# STLink-V2-1.net
KiCad netlist of a schematic drawn in Altium Designer
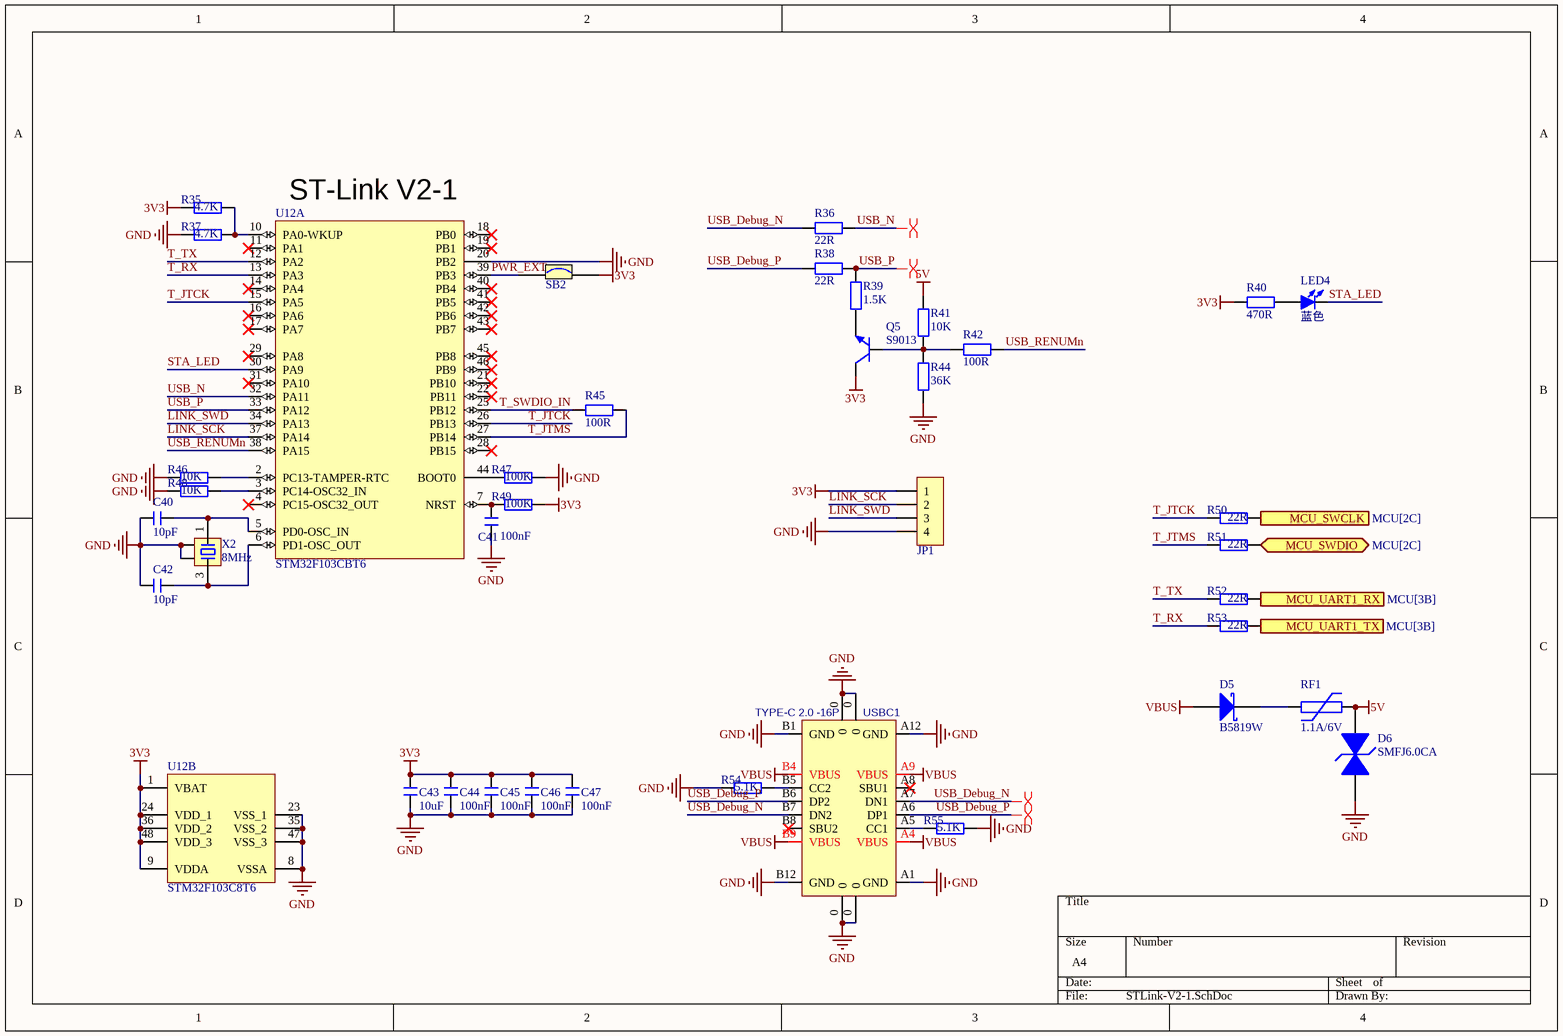
[diagram p0: STLink-V2-1.SchDoc]

(export (version "E")
  (design (tool "Eeschema 10.0.6"))
  (components
    (comp (ref "C40")
      (value "10pF")
      (footprint "C 0402_L")
      (description "无极性贴片电容")
      (fields (field (name "版权归属") "源创客"))
      (libsource (lib "源创客") (part "C"))
    )
    (comp (ref "C41")
      (value "100nF")
      (footprint "C 0402_L")
      (description "无极性贴片电容")
      (fields (field (name "版权归属") "源创客"))
      (libsource (lib "源创客") (part "C"))
    )
    (comp (ref "C42")
      (value "10pF")
      (footprint "C 0402_L")
      (description "无极性贴片电容")
      (fields (field (name "版权归属") "源创客"))
      (libsource (lib "源创客") (part "C"))
    )
    (comp (ref "C43")
      (value "10uF")
      (footprint "C 0402_L")
      (description "无极性贴片电容")
      (fields (field (name "版权归属") "源创客"))
      (libsource (lib "源创客") (part "C"))
    )
    (comp (ref "C44")
      (value "100nF")
      (footprint "C 0402_L")
      (description "无极性贴片电容")
      (fields (field (name "版权归属") "源创客"))
      (libsource (lib "源创客") (part "C"))
    )
    (comp (ref "C45")
      (value "100nF")
      (footprint "C 0402_L")
      (description "无极性贴片电容")
      (fields (field (name "版权归属") "源创客"))
      (libsource (lib "源创客") (part "C"))
    )
    (comp (ref "C46")
      (value "100nF")
      (footprint "C 0402_L")
      (description "无极性贴片电容")
      (fields (field (name "版权归属") "源创客"))
      (libsource (lib "源创客") (part "C"))
    )
    (comp (ref "C47")
      (value "100nF")
      (footprint "C 0402_L")
      (description "无极性贴片电容")
      (fields (field (name "版权归属") "源创客"))
      (libsource (lib "源创客") (part "C"))
    )
    (comp (ref "D5")
      (value "B5819W")
      (footprint "MCC-SOD123_V")
      (description "Schottky Barrier Rectifier, 1 A, 40 Vrm, -65 to 125 degC, 2-Pin SOD123, RoHS, Tape and Reel")
      (fields (field (name "MANUFACTURER") "Micro Commercial Components"))
      (libsource (lib "Altium Content Vault") (part "DSKY-AK-2"))
    )
    (comp (ref "D6")
      (value "SMFJ6.0CA")
      (footprint "SMFJ6.0CA")
      (description "贴片TVS瞬变抑制二极管")
      (libsource (lib "Display") (part "SMFJ6.0CA"))
    )
    (comp (ref "JP1")
      (value "HDR-1X4")
      (footprint "HDR2.54-LI-4P")
      (description "4P接插件")
      (libsource (lib "5.5 - 2.54mm(100mil)连接器(XH2.54)") (part "Header 4"))
    )
    (comp (ref "LED4")
      (value "蓝色")
      (footprint "LED 0603B")
      (description "贴片LED")
      (fields (field (name "版权归属") "源创客"))
      (libsource (lib "源创客") (part "LED-SMD"))
    )
    (comp (ref "Q5")
      (value "S9013")
      (footprint "SOT23-3L")
      (description "低频放大-NPN型")
      (fields (field (name "版权归属") "源创客"))
      (libsource (lib "源创客") (part "9013-SMD"))
    )
    (comp (ref "R35")
      (value "4.7K")
      (footprint "R 0402_L")
      (description "贴片电阻")
      (fields (field (name "版权归属") "源创客"))
      (libsource (lib "源创客") (part "R"))
    )
    (comp (ref "R36")
      (value "22R")
      (footprint "R 0402_L")
      (description "贴片电阻")
      (fields (field (name "版权归属") "源创客"))
      (libsource (lib "源创客") (part "R"))
    )
    (comp (ref "R37")
      (value "4.7K")
      (footprint "R 0402_L")
      (description "贴片电阻")
      (fields (field (name "版权归属") "源创客"))
      (libsource (lib "源创客") (part "R"))
    )
    (comp (ref "R38")
      (value "22R")
      (footprint "R 0402_L")
      (description "贴片电阻")
      (fields (field (name "版权归属") "源创客"))
      (libsource (lib "源创客") (part "R"))
    )
    (comp (ref "R39")
      (value "1.5K")
      (footprint "R 0402_L")
      (description "贴片电阻")
      (fields (field (name "版权归属") "源创客"))
      (libsource (lib "源创客") (part "R"))
    )
    (comp (ref "R40")
      (value "470R")
      (footprint "R 0402_L")
      (description "贴片电阻")
      (fields (field (name "版权归属") "源创客"))
      (libsource (lib "源创客") (part "R"))
    )
    (comp (ref "R41")
      (value "10K")
      (footprint "R 0402_L")
      (description "贴片电阻")
      (fields (field (name "版权归属") "源创客"))
      (libsource (lib "源创客") (part "R"))
    )
    (comp (ref "R42")
      (value "100R")
      (footprint "R 0402_L")
      (description "贴片电阻")
      (fields (field (name "版权归属") "源创客"))
      (libsource (lib "源创客") (part "R"))
    )
    (comp (ref "R44")
      (value "36K")
      (footprint "R 0402_L")
      (description "贴片电阻")
      (fields (field (name "版权归属") "源创客"))
      (libsource (lib "源创客") (part "R"))
    )
    (comp (ref "R45")
      (value "100R")
      (footprint "R 0402_L")
      (description "贴片电阻")
      (fields (field (name "版权归属") "源创客"))
      (libsource (lib "源创客") (part "R"))
    )
    (comp (ref "R46")
      (value "10K")
      (footprint "R 0402_L")
      (description "贴片电阻")
      (fields (field (name "版权归属") "源创客"))
      (libsource (lib "源创客") (part "R"))
    )
    (comp (ref "R47")
      (value "100K")
      (footprint "R 0402_L")
      (description "贴片电阻")
      (fields (field (name "版权归属") "源创客"))
      (libsource (lib "源创客") (part "R"))
    )
    (comp (ref "R48")
      (value "10K")
      (footprint "R 0402_L")
      (description "贴片电阻")
      (fields (field (name "版权归属") "源创客"))
      (libsource (lib "源创客") (part "R"))
    )
    (comp (ref "R49")
      (value "100K")
      (footprint "R 0402_L")
      (description "贴片电阻")
      (fields (field (name "版权归属") "源创客"))
      (libsource (lib "源创客") (part "R"))
    )
    (comp (ref "R50")
      (value "22R")
      (footprint "R 0402_L")
      (description "贴片电阻")
      (fields (field (name "版权归属") "源创客"))
      (libsource (lib "源创客") (part "R"))
    )
    (comp (ref "R51")
      (value "22R")
      (footprint "R 0402_L")
      (description "贴片电阻")
      (fields (field (name "版权归属") "源创客"))
      (libsource (lib "源创客") (part "R"))
    )
    (comp (ref "R52")
      (value "22R")
      (footprint "R 0402_L")
      (description "贴片电阻")
      (fields (field (name "版权归属") "源创客"))
      (libsource (lib "源创客") (part "R"))
    )
    (comp (ref "R53")
      (value "22R")
      (footprint "R 0402_L")
      (description "贴片电阻")
      (fields (field (name "版权归属") "源创客"))
      (libsource (lib "源创客") (part "R"))
    )
    (comp (ref "R54")
      (value "5.1K")
      (footprint "R 0402_L")
      (description "贴片电阻")
      (fields (field (name "版权归属") "源创客"))
      (libsource (lib "源创客") (part "R"))
    )
    (comp (ref "R55")
      (value "5.1K")
      (footprint "R 0402_L")
      (description "贴片电阻")
      (fields (field (name "版权归属") "源创客"))
      (libsource (lib "源创客") (part "R"))
    )
    (comp (ref "RF1")
      (value "1.1A/6V")
      (footprint "MF-NSMF110-2")
      (description "PPTC自恢复保险丝")
      (fields (field (name "版权归属") "源创客"))
      (libsource (lib "源创客") (part "PPTC"))
    )
    (comp (ref "SB2")
      (value "SelectBit")
      (footprint "SelectBit 0402")
      (description "跨接桥，用于选择不同的模式，可以用锡连上，或者焊上0R电阻")
      (libsource (lib "Display") (part "SelectBit"))
    )
    (comp (ref "U12")
      (value "STM32F103CBT6")
      (footprint "STM-LQFP48_L")
      (fields (field (name "PARTNUMBER") "STM32F103C8T6"))
      (libsource (lib "Altium Content Vault") (part "MC-ARM-STM32F103X8_B-SQ48"))
    )
    (comp (ref "USBC1")
      (value "TYPE-C 2.0 -16P")
      (footprint "USB-C-SMD_16P")
      (description "USB2.0_Type-C_16Pin母座")
      (libsource (lib "0.6 - 电源-以太网-音频-Type-C USB插座") (part "USB2.0_Type-C_16Pin"))
    )
    (comp (ref "X2")
      (value "8MHz")
      (footprint "XTAL-3225-4P")
      (description "4脚无源晶振(谐振器）")
      (libsource (lib "0.1 - 电阻-电容-电感-晶振-晶体-磁珠-电位器") (part "XTAL-4P"))
    )
  )
  (nets
    (net (code "1") (name "/LINK_SCK") (class "Default")
      (node (ref "JP1") (pin "2") (pinfunction "2_2") (pintype "passive"))
      (node (ref "U12") (pin "37") (pinfunction "PA14_37") (pintype "bidirectional"))
    )
    (net (code "2") (name "/LINK_SWD") (class "Default")
      (node (ref "JP1") (pin "3") (pinfunction "3_3") (pintype "passive"))
      (node (ref "U12") (pin "34") (pinfunction "PA13_34") (pintype "bidirectional"))
    )
    (net (code "3") (name "/MCU_SWCLK") (class "Default")
      (node (ref "R50") (pin "1") (pinfunction "1_1") (pintype "passive"))
    )
    (net (code "4") (name "/MCU_SWDIO") (class "Default")
      (node (ref "R51") (pin "1") (pinfunction "1_1") (pintype "passive"))
    )
    (net (code "5") (name "/MCU_UART1_RX") (class "Default")
      (node (ref "R52") (pin "1") (pinfunction "1_1") (pintype "passive"))
    )
    (net (code "6") (name "/MCU_UART1_TX") (class "Default")
      (node (ref "R53") (pin "1") (pinfunction "1_1") (pintype "passive"))
    )
    (net (code "7") (name "/PWR_EXT") (class "Default")
      (node (ref "SB2") (pin "1") (pinfunction "1_1") (pintype "passive"))
      (node (ref "U12") (pin "39") (pinfunction "PB3_39") (pintype "bidirectional"))
    )
    (net (code "8") (name "/STA_LED") (class "Default")
      (node (ref "LED4") (pin "2") (pinfunction "K_2") (pintype "passive"))
      (node (ref "U12") (pin "30") (pinfunction "PA9_30") (pintype "bidirectional"))
    )
    (net (code "9") (name "/T_JTCK") (class "Default")
      (node (ref "R50") (pin "2") (pinfunction "2_2") (pintype "passive"))
      (node (ref "U12") (pin "15") (pinfunction "PA5_15") (pintype "bidirectional"))
      (node (ref "U12") (pin "26") (pinfunction "PB13_26") (pintype "bidirectional"))
    )
    (net (code "10") (name "/T_JTMS") (class "Default")
      (node (ref "R45") (pin "1") (pinfunction "1_1") (pintype "passive"))
      (node (ref "R51") (pin "2") (pinfunction "2_2") (pintype "passive"))
      (node (ref "U12") (pin "27") (pinfunction "PB14_27") (pintype "bidirectional"))
    )
    (net (code "11") (name "/T_RX") (class "Default")
      (node (ref "R53") (pin "2") (pinfunction "2_2") (pintype "passive"))
      (node (ref "U12") (pin "13") (pinfunction "PA3_13") (pintype "bidirectional"))
    )
    (net (code "12") (name "/T_SWDIO_IN") (class "Default")
      (node (ref "R45") (pin "2") (pinfunction "2_2") (pintype "passive"))
      (node (ref "U12") (pin "25") (pinfunction "PB12_25") (pintype "bidirectional"))
    )
    (net (code "13") (name "/T_TX") (class "Default")
      (node (ref "R52") (pin "2") (pinfunction "2_2") (pintype "passive"))
      (node (ref "U12") (pin "12") (pinfunction "PA2_12") (pintype "bidirectional"))
    )
    (net (code "14") (name "/USB_Debug_N") (class "Default")
      (node (ref "R36") (pin "1") (pinfunction "1_1") (pintype "passive"))
      (node (ref "USBC1") (pin "A7") (pinfunction "DN1_A7") (pintype "passive"))
      (node (ref "USBC1") (pin "B7") (pinfunction "DN2_B7") (pintype "passive"))
    )
    (net (code "15") (name "/USB_Debug_P") (class "Default")
      (node (ref "R38") (pin "1") (pinfunction "1_1") (pintype "passive"))
      (node (ref "USBC1") (pin "A6") (pinfunction "DP1_A6") (pintype "passive"))
      (node (ref "USBC1") (pin "B6") (pinfunction "DP2_B6") (pintype "passive"))
    )
    (net (code "16") (name "/USB_N") (class "Default")
      (node (ref "R36") (pin "2") (pinfunction "2_2") (pintype "passive"))
      (node (ref "U12") (pin "32") (pinfunction "PA11_32") (pintype "bidirectional"))
    )
    (net (code "17") (name "/USB_P") (class "Default")
      (node (ref "R38") (pin "2") (pinfunction "2_2") (pintype "passive"))
      (node (ref "R39") (pin "2") (pinfunction "2_2") (pintype "passive"))
      (node (ref "U12") (pin "33") (pinfunction "PA12_33") (pintype "bidirectional"))
    )
    (net (code "18") (name "/USB_RENUMn") (class "Default")
      (node (ref "R42") (pin "1") (pinfunction "1_1") (pintype "passive"))
      (node (ref "U12") (pin "38") (pinfunction "PA15_38") (pintype "bidirectional"))
    )
    (net (code "19") (name "3V3") (class "Default")
      (node (ref "C43") (pin "2") (pinfunction "2_2") (pintype "passive"))
      (node (ref "C44") (pin "2") (pinfunction "2_2") (pintype "passive"))
      (node (ref "C45") (pin "2") (pinfunction "2_2") (pintype "passive"))
      (node (ref "C46") (pin "2") (pinfunction "2_2") (pintype "passive"))
      (node (ref "C47") (pin "2") (pinfunction "2_2") (pintype "passive"))
      (node (ref "JP1") (pin "1") (pinfunction "1_1") (pintype "passive"))
      (node (ref "Q5") (pin "3") (pinfunction "C_3") (pintype "passive"))
      (node (ref "R35") (pin "1") (pinfunction "1_1") (pintype "passive"))
      (node (ref "R40") (pin "2") (pinfunction "2_2") (pintype "passive"))
      (node (ref "R49") (pin "1") (pinfunction "1_1") (pintype "passive"))
      (node (ref "SB2") (pin "2") (pinfunction "2_2") (pintype "passive"))
      (node (ref "U12") (pin "1") (pinfunction "VBAT_1") (pintype "power_in"))
      (node (ref "U12") (pin "24") (pinfunction "VDD_1_24") (pintype "power_in"))
      (node (ref "U12") (pin "36") (pinfunction "VDD_2_36") (pintype "power_in"))
      (node (ref "U12") (pin "48") (pinfunction "VDD_3_48") (pintype "power_in"))
      (node (ref "U12") (pin "9") (pinfunction "VDDA_9") (pintype "power_in"))
    )
    (net (code "20") (name "5V") (class "Default")
      (node (ref "D6") (pin "2") (pinfunction "2_2") (pintype "passive"))
      (node (ref "R41") (pin "2") (pinfunction "2_2") (pintype "passive"))
      (node (ref "RF1") (pin "2") (pinfunction "2_2") (pintype "passive"))
    )
    (net (code "21") (name "GND") (class "Default")
      (node (ref "C40") (pin "2") (pinfunction "2_2") (pintype "passive"))
      (node (ref "C41") (pin "1") (pinfunction "1_1") (pintype "passive"))
      (node (ref "C42") (pin "2") (pinfunction "2_2") (pintype "passive"))
      (node (ref "C43") (pin "1") (pinfunction "1_1") (pintype "passive"))
      (node (ref "C44") (pin "1") (pinfunction "1_1") (pintype "passive"))
      (node (ref "C45") (pin "1") (pinfunction "1_1") (pintype "passive"))
      (node (ref "C46") (pin "1") (pinfunction "1_1") (pintype "passive"))
      (node (ref "C47") (pin "1") (pinfunction "1_1") (pintype "passive"))
      (node (ref "D6") (pin "1") (pinfunction "1_1") (pintype "passive"))
      (node (ref "JP1") (pin "4") (pinfunction "4_4") (pintype "passive"))
      (node (ref "R37") (pin "1") (pinfunction "1_1") (pintype "passive"))
      (node (ref "R44") (pin "1") (pinfunction "1_1") (pintype "passive"))
      (node (ref "R46") (pin "2") (pinfunction "2_2") (pintype "passive"))
      (node (ref "R47") (pin "1") (pinfunction "1_1") (pintype "passive"))
      (node (ref "R48") (pin "2") (pinfunction "2_2") (pintype "passive"))
      (node (ref "R54") (pin "2") (pinfunction "2_2") (pintype "passive"))
      (node (ref "R55") (pin "1") (pinfunction "1_1") (pintype "passive"))
      (node (ref "U12") (pin "20") (pinfunction "PB2_20") (pintype "passive"))
      (node (ref "U12") (pin "23") (pinfunction "VSS_1_23") (pintype "power_in"))
      (node (ref "U12") (pin "35") (pinfunction "VSS_2_35") (pintype "power_in"))
      (node (ref "U12") (pin "47") (pinfunction "VSS_3_47") (pintype "power_in"))
      (node (ref "U12") (pin "8") (pinfunction "VSSA_8") (pintype "power_in"))
      (node (ref "USBC1") (pin "0") (pinfunction "0_0") (pintype "passive"))
      (node (ref "USBC1") (pin "A1") (pinfunction "GND_A1") (pintype "passive"))
      (node (ref "USBC1") (pin "A12") (pinfunction "GND_A12") (pintype "passive"))
      (node (ref "USBC1") (pin "B1") (pinfunction "GND_B1") (pintype "passive"))
      (node (ref "USBC1") (pin "B12") (pinfunction "GND_B12") (pintype "passive"))
      (node (ref "X2") (pin "2") (pinfunction "2_2") (pintype "passive"))
      (node (ref "X2") (pin "4") (pinfunction "4_4") (pintype "passive"))
    )
    (net (code "22") (name "Net-(D5-K)") (class "Default")
      (node (ref "D5") (pin "2") (pinfunction "K_2") (pintype "passive"))
      (node (ref "RF1") (pin "1") (pinfunction "1_1") (pintype "passive"))
    )
    (net (code "23") (name "Net-(LED4-A)") (class "Default")
      (node (ref "LED4") (pin "1") (pinfunction "A_1") (pintype "passive"))
      (node (ref "R40") (pin "1") (pinfunction "1_1") (pintype "passive"))
    )
    (net (code "24") (name "Net-(Q5-B)") (class "Default")
      (node (ref "Q5") (pin "1") (pinfunction "B_1") (pintype "passive"))
      (node (ref "R41") (pin "1") (pinfunction "1_1") (pintype "passive"))
      (node (ref "R42") (pin "2") (pinfunction "2_2") (pintype "passive"))
      (node (ref "R44") (pin "2") (pinfunction "2_2") (pintype "passive"))
    )
    (net (code "25") (name "Net-(Q5-E)") (class "Default")
      (node (ref "Q5") (pin "2") (pinfunction "E_2") (pintype "passive"))
      (node (ref "R39") (pin "1") (pinfunction "1_1") (pintype "passive"))
    )
    (net (code "26") (name "Net-(U12A-BOOT0)") (class "Default")
      (node (ref "R47") (pin "2") (pinfunction "2_2") (pintype "passive"))
      (node (ref "U12") (pin "44") (pinfunction "BOOT0_44") (pintype "passive"))
    )
    (net (code "27") (name "Net-(U12A-NRST)") (class "Default")
      (node (ref "C41") (pin "2") (pinfunction "2_2") (pintype "passive"))
      (node (ref "R49") (pin "2") (pinfunction "2_2") (pintype "passive"))
      (node (ref "U12") (pin "7") (pinfunction "NRST_7") (pintype "bidirectional"))
    )
    (net (code "28") (name "Net-(U12A-PA0-WKUP)") (class "Default")
      (node (ref "R35") (pin "2") (pinfunction "2_2") (pintype "passive"))
      (node (ref "R37") (pin "2") (pinfunction "2_2") (pintype "passive"))
      (node (ref "U12") (pin "10") (pinfunction "PA0-WKUP_10") (pintype "bidirectional"))
    )
    (net (code "29") (name "Net-(U12A-PC13-TAMPER-RTC)") (class "Default")
      (node (ref "R46") (pin "1") (pinfunction "1_1") (pintype "passive"))
      (node (ref "U12") (pin "2") (pinfunction "PC13-TAMPER-RTC_2") (pintype "bidirectional"))
    )
    (net (code "30") (name "Net-(U12A-PC14-OSC32_IN)") (class "Default")
      (node (ref "R48") (pin "1") (pinfunction "1_1") (pintype "passive"))
      (node (ref "U12") (pin "3") (pinfunction "PC14-OSC32_IN_3") (pintype "bidirectional"))
    )
    (net (code "31") (name "Net-(U12A-PD0-OSC_IN)") (class "Default")
      (node (ref "C40") (pin "1") (pinfunction "1_1") (pintype "passive"))
      (node (ref "U12") (pin "5") (pinfunction "PD0-OSC_IN_5") (pintype "bidirectional"))
      (node (ref "X2") (pin "1") (pinfunction "1_1") (pintype "passive"))
    )
    (net (code "32") (name "Net-(U12A-PD1-OSC_OUT)") (class "Default")
      (node (ref "C42") (pin "1") (pinfunction "1_1") (pintype "passive"))
      (node (ref "U12") (pin "6") (pinfunction "PD1-OSC_OUT_6") (pintype "bidirectional"))
      (node (ref "X2") (pin "3") (pinfunction "3_3") (pintype "passive"))
    )
    (net (code "33") (name "Net-(USBC1-CC1)") (class "Default")
      (node (ref "R55") (pin "2") (pinfunction "2_2") (pintype "passive"))
      (node (ref "USBC1") (pin "A5") (pinfunction "CC1_A5") (pintype "passive"))
    )
    (net (code "34") (name "Net-(USBC1-CC2)") (class "Default")
      (node (ref "R54") (pin "1") (pinfunction "1_1") (pintype "passive"))
      (node (ref "USBC1") (pin "B5") (pinfunction "CC2_B5") (pintype "passive"))
    )
    (net (code "35") (name "VBUS") (class "Default")
      (node (ref "D5") (pin "1") (pinfunction "A_1") (pintype "passive"))
      (node (ref "USBC1") (pin "A4") (pinfunction "VBUS_A4") (pintype "passive"))
      (node (ref "USBC1") (pin "A9") (pinfunction "VBUS_A9") (pintype "passive"))
      (node (ref "USBC1") (pin "B4") (pinfunction "VBUS_B4") (pintype "passive"))
      (node (ref "USBC1") (pin "B9") (pinfunction "VBUS_B9") (pintype "passive"))
    )
    (net (code "36") (name "unconnected-(U12A-PA1-Pad11)") (class "Default")
      (node (ref "U12") (pin "11") (pinfunction "PA1_11") (pintype "bidirectional+no_connect"))
    )
    (net (code "37") (name "unconnected-(U12A-PA4-Pad14)") (class "Default")
      (node (ref "U12") (pin "14") (pinfunction "PA4_14") (pintype "bidirectional+no_connect"))
    )
    (net (code "38") (name "unconnected-(U12A-PA6-Pad16)") (class "Default")
      (node (ref "U12") (pin "16") (pinfunction "PA6_16") (pintype "bidirectional+no_connect"))
    )
    (net (code "39") (name "unconnected-(U12A-PA7-Pad17)") (class "Default")
      (node (ref "U12") (pin "17") (pinfunction "PA7_17") (pintype "bidirectional+no_connect"))
    )
    (net (code "40") (name "unconnected-(U12A-PA8-Pad29)") (class "Default")
      (node (ref "U12") (pin "29") (pinfunction "PA8_29") (pintype "bidirectional+no_connect"))
    )
    (net (code "41") (name "unconnected-(U12A-PA10-Pad31)") (class "Default")
      (node (ref "U12") (pin "31") (pinfunction "PA10_31") (pintype "bidirectional+no_connect"))
    )
    (net (code "42") (name "unconnected-(U12A-PB0-Pad18)") (class "Default")
      (node (ref "U12") (pin "18") (pinfunction "PB0_18") (pintype "bidirectional+no_connect"))
    )
    (net (code "43") (name "unconnected-(U12A-PB1-Pad19)") (class "Default")
      (node (ref "U12") (pin "19") (pinfunction "PB1_19") (pintype "bidirectional+no_connect"))
    )
    (net (code "44") (name "unconnected-(U12A-PB4-Pad40)") (class "Default")
      (node (ref "U12") (pin "40") (pinfunction "PB4_40") (pintype "bidirectional+no_connect"))
    )
    (net (code "45") (name "unconnected-(U12A-PB5-Pad41)") (class "Default")
      (node (ref "U12") (pin "41") (pinfunction "PB5_41") (pintype "bidirectional+no_connect"))
    )
    (net (code "46") (name "unconnected-(U12A-PB6-Pad42)") (class "Default")
      (node (ref "U12") (pin "42") (pinfunction "PB6_42") (pintype "bidirectional+no_connect"))
    )
    (net (code "47") (name "unconnected-(U12A-PB7-Pad43)") (class "Default")
      (node (ref "U12") (pin "43") (pinfunction "PB7_43") (pintype "bidirectional+no_connect"))
    )
    (net (code "48") (name "unconnected-(U12A-PB8-Pad45)") (class "Default")
      (node (ref "U12") (pin "45") (pinfunction "PB8_45") (pintype "bidirectional+no_connect"))
    )
    (net (code "49") (name "unconnected-(U12A-PB9-Pad46)") (class "Default")
      (node (ref "U12") (pin "46") (pinfunction "PB9_46") (pintype "bidirectional+no_connect"))
    )
    (net (code "50") (name "unconnected-(U12A-PB10-Pad21)") (class "Default")
      (node (ref "U12") (pin "21") (pinfunction "PB10_21") (pintype "bidirectional+no_connect"))
    )
    (net (code "51") (name "unconnected-(U12A-PB11-Pad22)") (class "Default")
      (node (ref "U12") (pin "22") (pinfunction "PB11_22") (pintype "bidirectional+no_connect"))
    )
    (net (code "52") (name "unconnected-(U12A-PB15-Pad28)") (class "Default")
      (node (ref "U12") (pin "28") (pinfunction "PB15_28") (pintype "bidirectional+no_connect"))
    )
    (net (code "53") (name "unconnected-(U12A-PC15-OSC32_OUT-Pad4)") (class "Default")
      (node (ref "U12") (pin "4") (pinfunction "PC15-OSC32_OUT_4") (pintype "bidirectional+no_connect"))
    )
    (net (code "54") (name "unconnected-(USBC1-SBU1-PadA8)") (class "Default")
      (node (ref "USBC1") (pin "A8") (pinfunction "SBU1_A8") (pintype "passive+no_connect"))
    )
    (net (code "55") (name "unconnected-(USBC1-SBU2-PadB8)") (class "Default")
      (node (ref "USBC1") (pin "B8") (pinfunction "SBU2_B8") (pintype "passive+no_connect"))
    )
  )
)
